# ArduinoInterface_v5.net
KiCad netlist of a schematic drawn in EAGLE
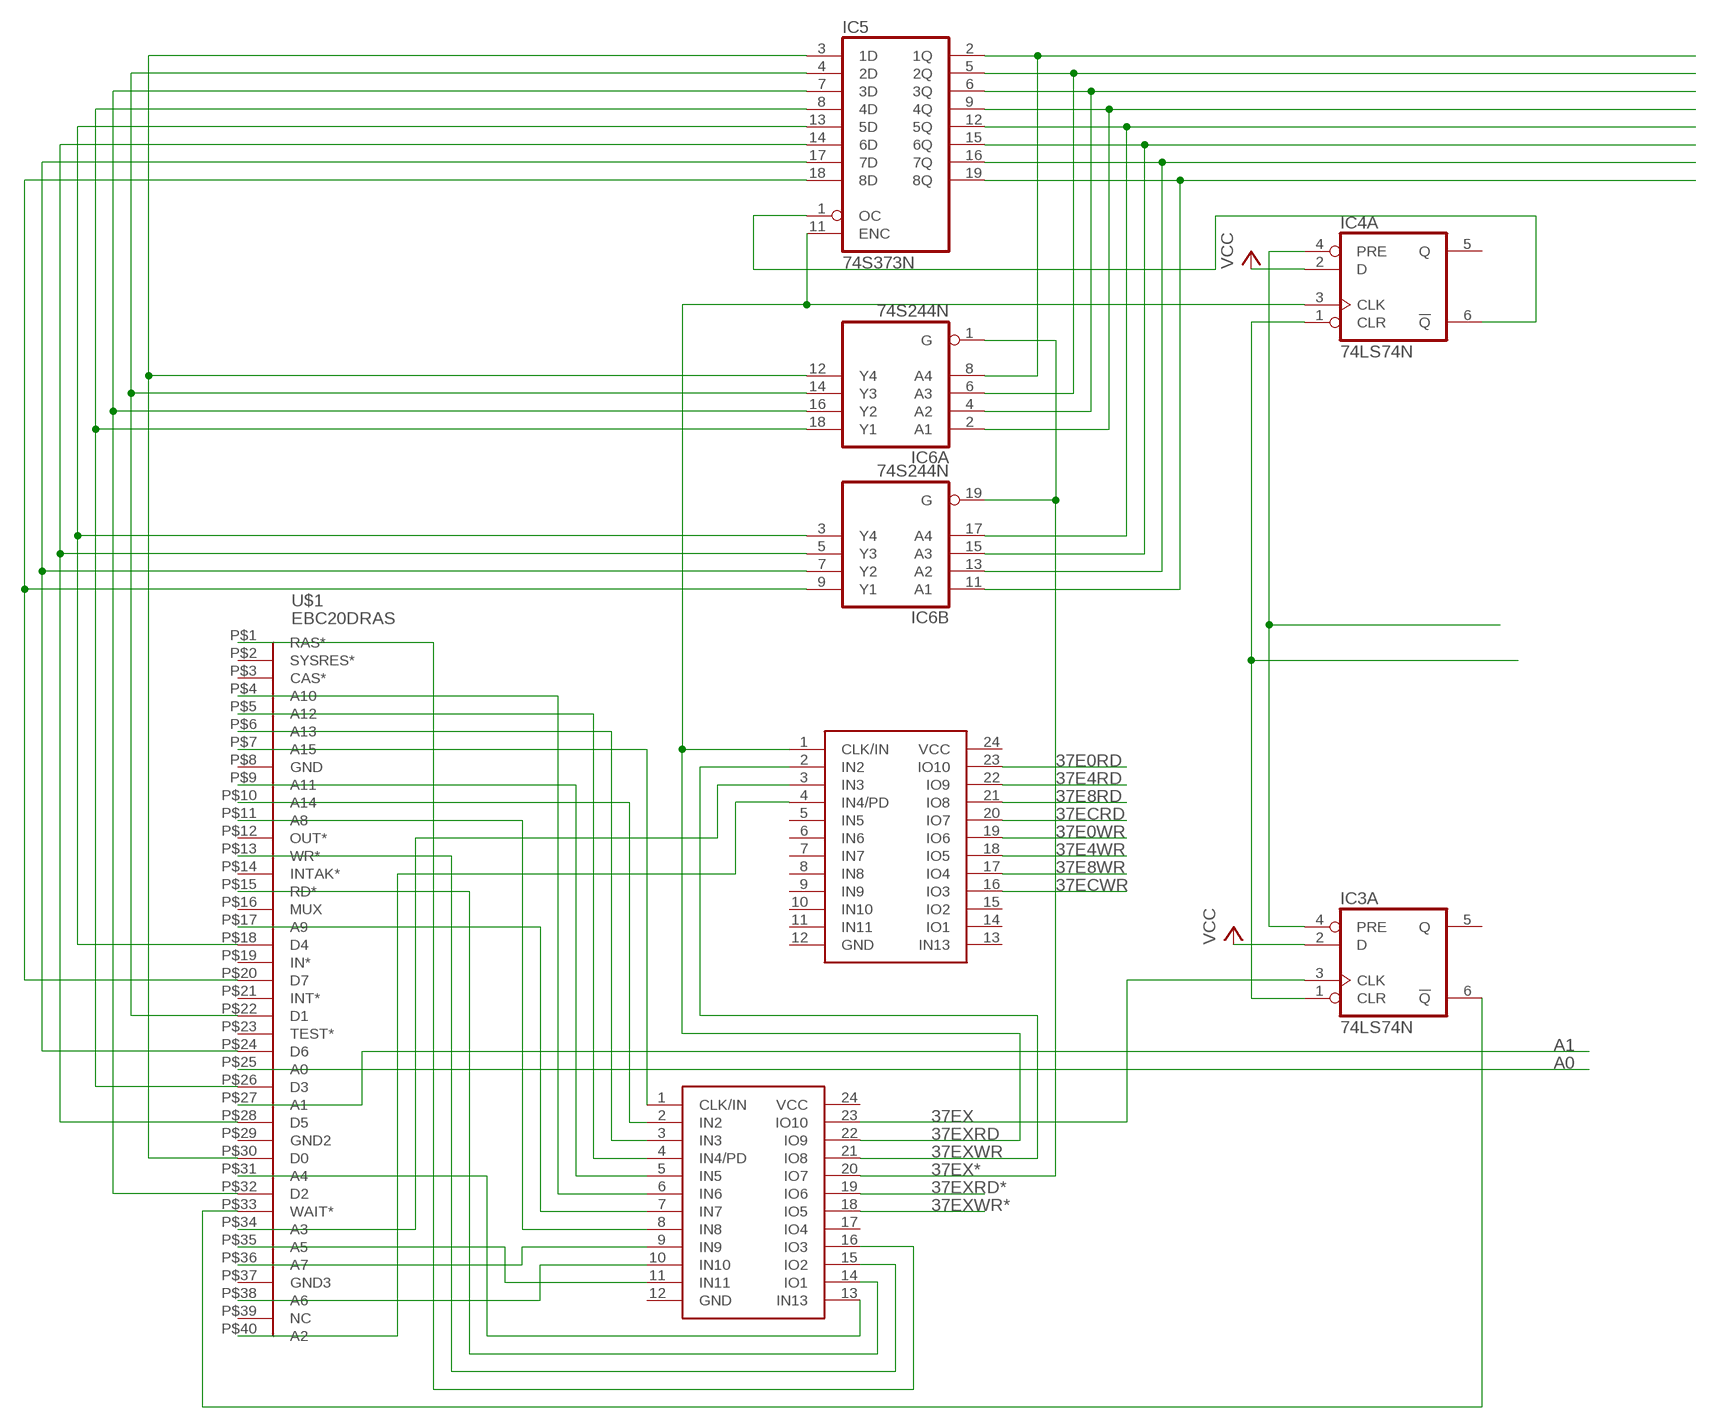
[diagram p0: schematic, sheet 1]

(export (version "E")
  (design (tool "Eeschema 10.0.6"))
  (components
    (comp (ref "IC1")
      (value "ATF22V10C")
      (footprint "eagle-import:DIP24SKI")
      (libsource (lib "eagle-import") (part "ATF22V10C"))
    )
    (comp (ref "IC2")
      (value "ATF22V10C")
      (footprint "eagle-import:DIP24SKI")
      (libsource (lib "eagle-import") (part "ATF22V10C"))
    )
    (comp (ref "IC3")
      (value "74LS74N")
      (footprint "eagle-import:DIL14")
      (libsource (lib "eagle-import") (part "7474NLS"))
    )
    (comp (ref "IC4")
      (value "74LS74N")
      (footprint "eagle-import:DIL14")
      (libsource (lib "eagle-import") (part "7474NLS"))
    )
    (comp (ref "IC5")
      (value "74S373N")
      (footprint "eagle-import:DIL20")
      (libsource (lib "eagle-import") (part "74373NS"))
    )
    (comp (ref "IC6")
      (value "74S244N")
      (footprint "eagle-import:DIL20")
      (libsource (lib "eagle-import") (part "74244NS"))
    )
    (comp (ref "U$1")
      (value "EBC20DRAS")
      (footprint "eagle-import:EBC20DRAS")
      (libsource (lib "eagle-import") (part "EBC20DRAS"))
    )
  )
  (nets
    (net (code "1") (name "/37E0RD") (class "Default")
      (node (ref "IC2") (pin "23") (pinfunction "IO10_23") (pintype "bidirectional"))
    )
    (net (code "2") (name "/37E0WR") (class "Default")
      (node (ref "IC2") (pin "19") (pinfunction "IO6_19") (pintype "bidirectional"))
    )
    (net (code "3") (name "/37E4RD") (class "Default")
      (node (ref "IC2") (pin "22") (pinfunction "IO9_22") (pintype "bidirectional"))
    )
    (net (code "4") (name "/37E4WR") (class "Default")
      (node (ref "IC2") (pin "18") (pinfunction "IO5_18") (pintype "bidirectional"))
    )
    (net (code "5") (name "/37E8RD") (class "Default")
      (node (ref "IC2") (pin "21") (pinfunction "IO8_21") (pintype "bidirectional"))
    )
    (net (code "6") (name "/37E8WR") (class "Default")
      (node (ref "IC2") (pin "17") (pinfunction "IO4_17") (pintype "bidirectional"))
    )
    (net (code "7") (name "/37ECRD") (class "Default")
      (node (ref "IC2") (pin "20") (pinfunction "IO7_20") (pintype "bidirectional"))
    )
    (net (code "8") (name "/37ECWR") (class "Default")
      (node (ref "IC2") (pin "16") (pinfunction "IO3_16") (pintype "bidirectional"))
    )
    (net (code "9") (name "/37EX") (class "Default")
      (node (ref "IC1") (pin "23") (pinfunction "IO10_23") (pintype "bidirectional"))
      (node (ref "IC3") (pin "3") (pinfunction "CLK_3") (pintype "input"))
    )
    (net (code "10") (name "/37EX*") (class "Default")
      (node (ref "IC1") (pin "20") (pinfunction "IO7_20") (pintype "bidirectional"))
      (node (ref "IC6") (pin "1") (pinfunction "G_1") (pintype "input"))
      (node (ref "IC6") (pin "19") (pinfunction "G_19") (pintype "input"))
    )
    (net (code "11") (name "/37EXRD") (class "Default")
      (node (ref "IC1") (pin "22") (pinfunction "IO9_22") (pintype "bidirectional"))
      (node (ref "IC2") (pin "1") (pinfunction "CLK/IN_1") (pintype "bidirectional"))
      (node (ref "IC4") (pin "3") (pinfunction "CLK_3") (pintype "input"))
      (node (ref "IC5") (pin "11") (pinfunction "ENC_11") (pintype "input"))
    )
    (net (code "12") (name "/37EXRD*") (class "Default")
      (node (ref "IC1") (pin "19") (pinfunction "IO6_19") (pintype "bidirectional"))
    )
    (net (code "13") (name "/37EXWR") (class "Default")
      (node (ref "IC1") (pin "21") (pinfunction "IO8_21") (pintype "bidirectional"))
      (node (ref "IC2") (pin "2") (pinfunction "IN2_2") (pintype "bidirectional"))
    )
    (net (code "14") (name "/37EXWR*") (class "Default")
      (node (ref "IC1") (pin "18") (pinfunction "IO5_18") (pintype "bidirectional"))
    )
    (net (code "15") (name "/A0") (class "Default")
      (node (ref "U$1") (pin "P$25") (pinfunction "A0_P$25") (pintype "bidirectional"))
    )
    (net (code "16") (name "/A1") (class "Default")
      (node (ref "U$1") (pin "P$27") (pinfunction "A1_P$27") (pintype "bidirectional"))
    )
    (net (code "17") (name "Net-(IC1-CLK{slash}IN)") (class "Default")
      (node (ref "IC1") (pin "1") (pinfunction "CLK/IN_1") (pintype "bidirectional"))
      (node (ref "U$1") (pin "P$7") (pinfunction "A15_P$7") (pintype "bidirectional"))
    )
    (net (code "18") (name "Net-(IC1-IN2)") (class "Default")
      (node (ref "IC1") (pin "2") (pinfunction "IN2_2") (pintype "bidirectional"))
      (node (ref "U$1") (pin "P$10") (pinfunction "A14_P$10") (pintype "bidirectional"))
    )
    (net (code "19") (name "Net-(IC1-IN3)") (class "Default")
      (node (ref "IC1") (pin "3") (pinfunction "IN3_3") (pintype "bidirectional"))
      (node (ref "U$1") (pin "P$6") (pinfunction "A13_P$6") (pintype "bidirectional"))
    )
    (net (code "20") (name "Net-(IC1-IN4{slash}PD)") (class "Default")
      (node (ref "IC1") (pin "4") (pinfunction "IN4/PD_4") (pintype "bidirectional"))
      (node (ref "U$1") (pin "P$5") (pinfunction "A12_P$5") (pintype "bidirectional"))
    )
    (net (code "21") (name "Net-(IC1-IN5)") (class "Default")
      (node (ref "IC1") (pin "5") (pinfunction "IN5_5") (pintype "bidirectional"))
      (node (ref "U$1") (pin "P$9") (pinfunction "A11_P$9") (pintype "bidirectional"))
    )
    (net (code "22") (name "Net-(IC1-IN6)") (class "Default")
      (node (ref "IC1") (pin "6") (pinfunction "IN6_6") (pintype "bidirectional"))
      (node (ref "U$1") (pin "P$4") (pinfunction "A10_P$4") (pintype "bidirectional"))
    )
    (net (code "23") (name "Net-(IC1-IN7)") (class "Default")
      (node (ref "IC1") (pin "7") (pinfunction "IN7_7") (pintype "bidirectional"))
      (node (ref "U$1") (pin "P$17") (pinfunction "A9_P$17") (pintype "bidirectional"))
    )
    (net (code "24") (name "Net-(IC1-IN8)") (class "Default")
      (node (ref "IC1") (pin "8") (pinfunction "IN8_8") (pintype "bidirectional"))
      (node (ref "U$1") (pin "P$11") (pinfunction "A8_P$11") (pintype "bidirectional"))
    )
    (net (code "25") (name "Net-(IC1-IN9)") (class "Default")
      (node (ref "IC1") (pin "9") (pinfunction "IN9_9") (pintype "bidirectional"))
      (node (ref "U$1") (pin "P$36") (pinfunction "A7_P$36") (pintype "bidirectional"))
    )
    (net (code "26") (name "Net-(IC1-IN10)") (class "Default")
      (node (ref "IC1") (pin "10") (pinfunction "IN10_10") (pintype "bidirectional"))
      (node (ref "U$1") (pin "P$38") (pinfunction "A6_P$38") (pintype "bidirectional"))
    )
    (net (code "27") (name "Net-(IC1-IN11)") (class "Default")
      (node (ref "IC1") (pin "11") (pinfunction "IN11_11") (pintype "bidirectional"))
      (node (ref "U$1") (pin "P$35") (pinfunction "A5_P$35") (pintype "bidirectional"))
    )
    (net (code "28") (name "Net-(IC1-IN13)") (class "Default")
      (node (ref "IC1") (pin "13") (pinfunction "IN13_13") (pintype "bidirectional"))
      (node (ref "U$1") (pin "P$31") (pinfunction "A4_P$31") (pintype "bidirectional"))
    )
    (net (code "29") (name "Net-(IC1-IO1)") (class "Default")
      (node (ref "IC1") (pin "14") (pinfunction "IO1_14") (pintype "bidirectional"))
      (node (ref "U$1") (pin "P$15") (pinfunction "RD*_P$15") (pintype "bidirectional"))
    )
    (net (code "30") (name "Net-(IC1-IO2)") (class "Default")
      (node (ref "IC1") (pin "15") (pinfunction "IO2_15") (pintype "bidirectional"))
      (node (ref "U$1") (pin "P$13") (pinfunction "WR*_P$13") (pintype "bidirectional"))
    )
    (net (code "31") (name "Net-(IC1-IO3)") (class "Default")
      (node (ref "IC1") (pin "16") (pinfunction "IO3_16") (pintype "bidirectional"))
      (node (ref "U$1") (pin "P$1") (pinfunction "RAS*_P$1") (pintype "bidirectional"))
    )
    (net (code "32") (name "Net-(IC2-IN3)") (class "Default")
      (node (ref "IC2") (pin "3") (pinfunction "IN3_3") (pintype "bidirectional"))
      (node (ref "U$1") (pin "P$34") (pinfunction "A3_P$34") (pintype "bidirectional"))
    )
    (net (code "33") (name "Net-(IC2-IN4{slash}PD)") (class "Default")
      (node (ref "IC2") (pin "4") (pinfunction "IN4/PD_4") (pintype "bidirectional"))
      (node (ref "U$1") (pin "P$40") (pinfunction "A2_P$40") (pintype "bidirectional"))
    )
    (net (code "34") (name "Net-(IC3A-CLR)") (class "Default")
      (node (ref "IC3") (pin "1") (pinfunction "CLR_1") (pintype "input"))
      (node (ref "IC4") (pin "1") (pinfunction "CLR_1") (pintype "input"))
    )
    (net (code "35") (name "Net-(IC3A-PRE)") (class "Default")
      (node (ref "IC3") (pin "4") (pinfunction "PRE_4") (pintype "input"))
      (node (ref "IC4") (pin "4") (pinfunction "PRE_4") (pintype "input"))
    )
    (net (code "36") (name "Net-(IC3A-~{Q})") (class "Default")
      (node (ref "IC3") (pin "6") (pinfunction "~{Q}_6") (pintype "output"))
      (node (ref "U$1") (pin "P$33") (pinfunction "WAIT*_P$33") (pintype "bidirectional"))
    )
    (net (code "37") (name "Net-(IC4A-~{Q})") (class "Default")
      (node (ref "IC4") (pin "6") (pinfunction "~{Q}_6") (pintype "output"))
      (node (ref "IC5") (pin "1") (pinfunction "OC_1") (pintype "input"))
    )
    (net (code "38") (name "Net-(IC5A-1D)") (class "Default")
      (node (ref "IC5") (pin "3") (pinfunction "1D_3") (pintype "input"))
      (node (ref "IC6") (pin "12") (pinfunction "Y4_12") (pintype "tri_state"))
      (node (ref "U$1") (pin "P$30") (pinfunction "D0_P$30") (pintype "bidirectional"))
    )
    (net (code "39") (name "Net-(IC5A-1Q)") (class "Default")
      (node (ref "IC5") (pin "2") (pinfunction "1Q_2") (pintype "tri_state"))
      (node (ref "IC6") (pin "8") (pinfunction "A4_8") (pintype "input"))
    )
    (net (code "40") (name "Net-(IC5A-2D)") (class "Default")
      (node (ref "IC5") (pin "4") (pinfunction "2D_4") (pintype "input"))
      (node (ref "IC6") (pin "14") (pinfunction "Y3_14") (pintype "tri_state"))
      (node (ref "U$1") (pin "P$22") (pinfunction "D1_P$22") (pintype "bidirectional"))
    )
    (net (code "41") (name "Net-(IC5A-2Q)") (class "Default")
      (node (ref "IC5") (pin "5") (pinfunction "2Q_5") (pintype "tri_state"))
      (node (ref "IC6") (pin "6") (pinfunction "A3_6") (pintype "input"))
    )
    (net (code "42") (name "Net-(IC5A-3D)") (class "Default")
      (node (ref "IC5") (pin "7") (pinfunction "3D_7") (pintype "input"))
      (node (ref "IC6") (pin "16") (pinfunction "Y2_16") (pintype "tri_state"))
      (node (ref "U$1") (pin "P$32") (pinfunction "D2_P$32") (pintype "bidirectional"))
    )
    (net (code "43") (name "Net-(IC5A-3Q)") (class "Default")
      (node (ref "IC5") (pin "6") (pinfunction "3Q_6") (pintype "tri_state"))
      (node (ref "IC6") (pin "4") (pinfunction "A2_4") (pintype "input"))
    )
    (net (code "44") (name "Net-(IC5A-4D)") (class "Default")
      (node (ref "IC5") (pin "8") (pinfunction "4D_8") (pintype "input"))
      (node (ref "IC6") (pin "18") (pinfunction "Y1_18") (pintype "tri_state"))
      (node (ref "U$1") (pin "P$26") (pinfunction "D3_P$26") (pintype "bidirectional"))
    )
    (net (code "45") (name "Net-(IC5A-4Q)") (class "Default")
      (node (ref "IC5") (pin "9") (pinfunction "4Q_9") (pintype "tri_state"))
      (node (ref "IC6") (pin "2") (pinfunction "A1_2") (pintype "input"))
    )
    (net (code "46") (name "Net-(IC5A-5D)") (class "Default")
      (node (ref "IC5") (pin "13") (pinfunction "5D_13") (pintype "input"))
      (node (ref "IC6") (pin "3") (pinfunction "Y4_3") (pintype "tri_state"))
      (node (ref "U$1") (pin "P$18") (pinfunction "D4_P$18") (pintype "bidirectional"))
    )
    (net (code "47") (name "Net-(IC5A-5Q)") (class "Default")
      (node (ref "IC5") (pin "12") (pinfunction "5Q_12") (pintype "tri_state"))
      (node (ref "IC6") (pin "17") (pinfunction "A4_17") (pintype "input"))
    )
    (net (code "48") (name "Net-(IC5A-6D)") (class "Default")
      (node (ref "IC5") (pin "14") (pinfunction "6D_14") (pintype "input"))
      (node (ref "IC6") (pin "5") (pinfunction "Y3_5") (pintype "tri_state"))
      (node (ref "U$1") (pin "P$28") (pinfunction "D5_P$28") (pintype "bidirectional"))
    )
    (net (code "49") (name "Net-(IC5A-6Q)") (class "Default")
      (node (ref "IC5") (pin "15") (pinfunction "6Q_15") (pintype "tri_state"))
      (node (ref "IC6") (pin "15") (pinfunction "A3_15") (pintype "input"))
    )
    (net (code "50") (name "Net-(IC5A-7D)") (class "Default")
      (node (ref "IC5") (pin "17") (pinfunction "7D_17") (pintype "input"))
      (node (ref "IC6") (pin "7") (pinfunction "Y2_7") (pintype "tri_state"))
      (node (ref "U$1") (pin "P$24") (pinfunction "D6_P$24") (pintype "bidirectional"))
    )
    (net (code "51") (name "Net-(IC5A-7Q)") (class "Default")
      (node (ref "IC5") (pin "16") (pinfunction "7Q_16") (pintype "tri_state"))
      (node (ref "IC6") (pin "13") (pinfunction "A2_13") (pintype "input"))
    )
    (net (code "52") (name "Net-(IC5A-8D)") (class "Default")
      (node (ref "IC5") (pin "18") (pinfunction "8D_18") (pintype "input"))
      (node (ref "IC6") (pin "9") (pinfunction "Y1_9") (pintype "tri_state"))
      (node (ref "U$1") (pin "P$20") (pinfunction "D7_P$20") (pintype "bidirectional"))
    )
    (net (code "53") (name "Net-(IC5A-8Q)") (class "Default")
      (node (ref "IC5") (pin "19") (pinfunction "8Q_19") (pintype "tri_state"))
      (node (ref "IC6") (pin "11") (pinfunction "A1_11") (pintype "input"))
    )
    (net (code "54") (name "VCC") (class "Default")
      (node (ref "IC3") (pin "2") (pinfunction "D_2") (pintype "input"))
      (node (ref "IC4") (pin "2") (pinfunction "D_2") (pintype "input"))
    )
    (net (code "55") (name "unconnected-(IC1-GND-Pad12)") (class "Default")
      (node (ref "IC1") (pin "12") (pinfunction "GND_12") (pintype "bidirectional"))
    )
    (net (code "56") (name "unconnected-(IC1-IO4-Pad17)") (class "Default")
      (node (ref "IC1") (pin "17") (pinfunction "IO4_17") (pintype "bidirectional"))
    )
    (net (code "57") (name "unconnected-(IC1-VCC-Pad24)") (class "Default")
      (node (ref "IC1") (pin "24") (pinfunction "VCC_24") (pintype "bidirectional"))
    )
    (net (code "58") (name "unconnected-(IC2-GND-Pad12)") (class "Default")
      (node (ref "IC2") (pin "12") (pinfunction "GND_12") (pintype "bidirectional"))
    )
    (net (code "59") (name "unconnected-(IC2-IN5-Pad5)") (class "Default")
      (node (ref "IC2") (pin "5") (pinfunction "IN5_5") (pintype "bidirectional"))
    )
    (net (code "60") (name "unconnected-(IC2-IN6-Pad6)") (class "Default")
      (node (ref "IC2") (pin "6") (pinfunction "IN6_6") (pintype "bidirectional"))
    )
    (net (code "61") (name "unconnected-(IC2-IN7-Pad7)") (class "Default")
      (node (ref "IC2") (pin "7") (pinfunction "IN7_7") (pintype "bidirectional"))
    )
    (net (code "62") (name "unconnected-(IC2-IN8-Pad8)") (class "Default")
      (node (ref "IC2") (pin "8") (pinfunction "IN8_8") (pintype "bidirectional"))
    )
    (net (code "63") (name "unconnected-(IC2-IN9-Pad9)") (class "Default")
      (node (ref "IC2") (pin "9") (pinfunction "IN9_9") (pintype "bidirectional"))
    )
    (net (code "64") (name "unconnected-(IC2-IN10-Pad10)") (class "Default")
      (node (ref "IC2") (pin "10") (pinfunction "IN10_10") (pintype "bidirectional"))
    )
    (net (code "65") (name "unconnected-(IC2-IN11-Pad11)") (class "Default")
      (node (ref "IC2") (pin "11") (pinfunction "IN11_11") (pintype "bidirectional"))
    )
    (net (code "66") (name "unconnected-(IC2-IN13-Pad13)") (class "Default")
      (node (ref "IC2") (pin "13") (pinfunction "IN13_13") (pintype "bidirectional"))
    )
    (net (code "67") (name "unconnected-(IC2-IO1-Pad14)") (class "Default")
      (node (ref "IC2") (pin "14") (pinfunction "IO1_14") (pintype "bidirectional"))
    )
    (net (code "68") (name "unconnected-(IC2-IO2-Pad15)") (class "Default")
      (node (ref "IC2") (pin "15") (pinfunction "IO2_15") (pintype "bidirectional"))
    )
    (net (code "69") (name "unconnected-(IC2-VCC-Pad24)") (class "Default")
      (node (ref "IC2") (pin "24") (pinfunction "VCC_24") (pintype "bidirectional"))
    )
    (net (code "70") (name "unconnected-(IC3A-Q-Pad5)") (class "Default")
      (node (ref "IC3") (pin "5") (pinfunction "Q_5") (pintype "output"))
    )
    (net (code "71") (name "unconnected-(IC4A-Q-Pad5)") (class "Default")
      (node (ref "IC4") (pin "5") (pinfunction "Q_5") (pintype "output"))
    )
    (net (code "72") (name "unconnected-(U$1-CAS*-PadP$3)") (class "Default")
      (node (ref "U$1") (pin "P$3") (pinfunction "CAS*_P$3") (pintype "bidirectional"))
    )
    (net (code "73") (name "unconnected-(U$1-GND-PadP$8)") (class "Default")
      (node (ref "U$1") (pin "P$8") (pinfunction "GND_P$8") (pintype "bidirectional"))
    )
    (net (code "74") (name "unconnected-(U$1-GND2-PadP$29)") (class "Default")
      (node (ref "U$1") (pin "P$29") (pinfunction "GND2_P$29") (pintype "bidirectional"))
    )
    (net (code "75") (name "unconnected-(U$1-GND3-PadP$37)") (class "Default")
      (node (ref "U$1") (pin "P$37") (pinfunction "GND3_P$37") (pintype "bidirectional"))
    )
    (net (code "76") (name "unconnected-(U$1-IN*-PadP$19)") (class "Default")
      (node (ref "U$1") (pin "P$19") (pinfunction "IN*_P$19") (pintype "bidirectional"))
    )
    (net (code "77") (name "unconnected-(U$1-INT*-PadP$21)") (class "Default")
      (node (ref "U$1") (pin "P$21") (pinfunction "INT*_P$21") (pintype "bidirectional"))
    )
    (net (code "78") (name "unconnected-(U$1-INTAK*-PadP$14)") (class "Default")
      (node (ref "U$1") (pin "P$14") (pinfunction "INTAK*_P$14") (pintype "bidirectional"))
    )
    (net (code "79") (name "unconnected-(U$1-MUX-PadP$16)") (class "Default")
      (node (ref "U$1") (pin "P$16") (pinfunction "MUX_P$16") (pintype "bidirectional"))
    )
    (net (code "80") (name "unconnected-(U$1-NC-PadP$39)") (class "Default")
      (node (ref "U$1") (pin "P$39") (pinfunction "NC_P$39") (pintype "bidirectional"))
    )
    (net (code "81") (name "unconnected-(U$1-OUT*-PadP$12)") (class "Default")
      (node (ref "U$1") (pin "P$12") (pinfunction "OUT*_P$12") (pintype "bidirectional"))
    )
    (net (code "82") (name "unconnected-(U$1-SYSRES*-PadP$2)") (class "Default")
      (node (ref "U$1") (pin "P$2") (pinfunction "SYSRES*_P$2") (pintype "bidirectional"))
    )
    (net (code "83") (name "unconnected-(U$1-TEST*-PadP$23)") (class "Default")
      (node (ref "U$1") (pin "P$23") (pinfunction "TEST*_P$23") (pintype "bidirectional"))
    )
  )
)
